# SystemPower.net
KiCad netlist of a schematic drawn in Altium Designer
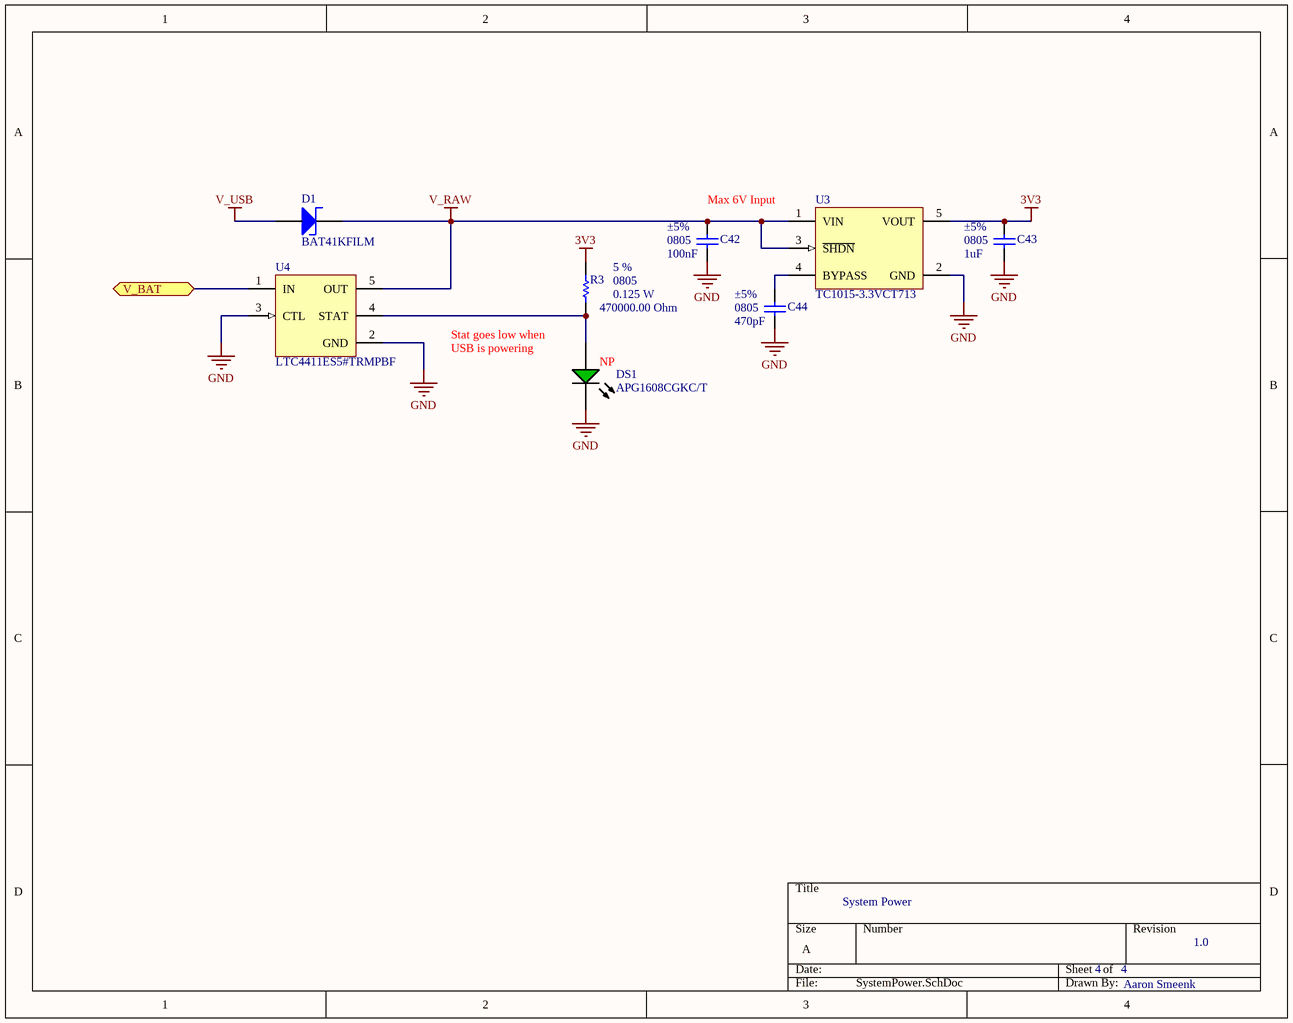
[diagram p0: SystemPower.SchDoc]

(export (version "E")
  (design (tool "Eeschema 10.0.6"))
  (components
    (comp (ref "C42")
      (value "100nF")
      (footprint "CAPC0805(2012)100_M")
      (description "CAP 100nF 6.3V ±5% 0805 (2012 Metric) Thickness 1mm SMD")
      (fields
        (field (name "TOLERANCE") "±5%")
        (field (name "CASE-EIA") "0805")
        (field (name "Comment") "CAP 100nF 6.3V 0805(2012)")
      )
      (libsource (lib "Altium Content Vault") (part "CMP-1036-04390-1"))
    )
    (comp (ref "C43")
      (value "1uF")
      (footprint "CAPC0805(2012)100_L")
      (description "CAP 1uF 6.3V ±5% 0805 (2012 Metric) Thickness 1mm SMD")
      (fields
        (field (name "TOLERANCE") "±5%")
        (field (name "CASE-EIA") "0805")
        (field (name "Comment") "CAP 1uF 6.3V 0805(2012)")
      )
      (libsource (lib "Altium Content Vault") (part "CMP-1036-04730-1"))
    )
    (comp (ref "C44")
      (value "470pF")
      (footprint "CAPC0805(2012)100_N")
      (description "CAP 470pF 6.3V ±5% 0805 (2012 Metric) Thickness 1mm SMD")
      (fields
        (field (name "CASE-EIA") "0805")
        (field (name "TOLERANCE") "±5%")
        (field (name "Comment") "CAP 470pF 6.3V 0805(2012)")
      )
      (libsource (lib "Altium Content Vault") (part "CMP-1036-02639-1"))
    )
    (comp (ref "D1")
      (value "BAT41KFILM")
      (footprint "BAT41KFILM")
      (description "DIODE SCHOTTKY 100V 200MA SOD523")
      (libsource (lib "schlib") (part "BAT41KFILM"))
    )
    (comp (ref "DS1")
      (value "APG1608CGKC/T")
      (footprint "KING-LED0603-25-GREEN_V")
      (description "LED, SMT, 0603(1608), 0.25mm Thickness, Green")
      (libsource (lib "Altium Content Vault") (part "CMP-0239-00001-1"))
    )
    (comp (ref "R3")
      (value "470000.00 Ohm")
      (footprint "RESC0805(2012)_L")
      (description "470K 0.125W 5% 0805 (2012 Metric)  SMD")
      (fields
        (field (name "POWER") "0.125 W")
        (field (name "TOLERANCE") "5 %")
        (field (name "CASE-EIA") "0805")
        (field (name "Comment") "470K 5% 0805(2012)")
      )
      (libsource (lib "Altium Content Vault") (part "CMP-1013-00138-1"))
    )
    (comp (ref "U3")
      (value "TC1015-3.3VCT713")
      (footprint "SOT-23-CT5_N")
      (libsource (lib "Altium Content Vault") (part "PM-LINEREG-TC1014-IL5"))
    )
    (comp (ref "U4")
      (value "LTC4411ES5#TRMPBF")
      (footprint "LT-S5-5-TSOT-23_L")
      (fields (field (name "MANUFACTURER") "Linear Technology"))
      (libsource (lib "Altium Content Vault") (part "LT-LTC4411-S5-5"))
    )
  )
  (nets
    (net (code "1") (name "/V_BAT") (class "Default")
      (node (ref "U4") (pin "1") (pinfunction "IN_1") (pintype "power_in"))
    )
    (net (code "2") (name "3V3") (class "Default")
      (node (ref "C43") (pin "2") (pinfunction "2_2") (pintype "passive"))
      (node (ref "R3") (pin "2") (pinfunction "2_2") (pintype "passive"))
      (node (ref "U3") (pin "5") (pinfunction "VOUT_5") (pintype "power_in"))
    )
    (net (code "3") (name "GND") (class "Default")
      (node (ref "C42") (pin "1") (pinfunction "1_1") (pintype "passive"))
      (node (ref "C43") (pin "1") (pinfunction "1_1") (pintype "passive"))
      (node (ref "C44") (pin "1") (pinfunction "1_1") (pintype "passive"))
      (node (ref "DS1") (pin "2") (pinfunction "K_2") (pintype "passive"))
      (node (ref "U3") (pin "2") (pinfunction "GND_2") (pintype "power_in"))
      (node (ref "U4") (pin "2") (pinfunction "GND_2") (pintype "power_in"))
      (node (ref "U4") (pin "3") (pinfunction "CTL_3") (pintype "input"))
    )
    (net (code "4") (name "Net-(DS1-A)") (class "Default")
      (node (ref "DS1") (pin "1") (pinfunction "A_1") (pintype "passive"))
      (node (ref "R3") (pin "1") (pinfunction "1_1") (pintype "passive"))
      (node (ref "U4") (pin "4") (pinfunction "STAT_4") (pintype "tri_state"))
    )
    (net (code "5") (name "Net-(U3-BYPASS)") (class "Default")
      (node (ref "C44") (pin "2") (pinfunction "2_2") (pintype "passive"))
      (node (ref "U3") (pin "4") (pinfunction "BYPASS_4") (pintype "passive"))
    )
    (net (code "6") (name "V_RAW") (class "Default")
      (node (ref "C42") (pin "2") (pinfunction "2_2") (pintype "passive"))
      (node (ref "D1") (pin "1") (pinfunction "1_1") (pintype "passive"))
      (node (ref "U3") (pin "1") (pinfunction "VIN_1") (pintype "power_in"))
      (node (ref "U3") (pin "3") (pinfunction "~{SHDN}_3") (pintype "input"))
      (node (ref "U4") (pin "5") (pinfunction "OUT_5") (pintype "power_in"))
    )
    (net (code "7") (name "V_USB") (class "Default")
      (node (ref "D1") (pin "2") (pinfunction "2_2") (pintype "passive"))
    )
  )
)
